# Sheet_Sensor.net
KiCad netlist of a schematic drawn in Altium Designer
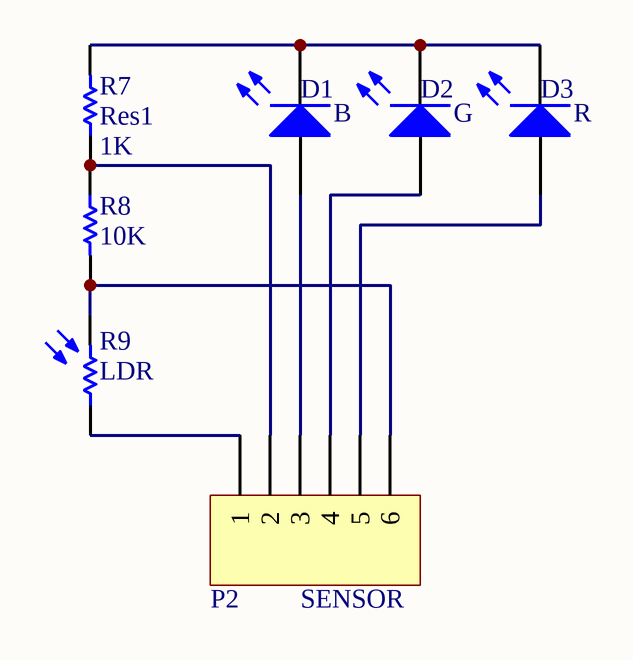
[diagram p0: Sheet_Sensor.SchDoc]

(export (version "E")
  (design (tool "Eeschema 10.0.6"))
  (components
    (comp (ref "D1")
      (value "B")
      (footprint "LED")
      (description "Typical RED GaAs LED")
      (fields (field (name "PUBLISHER") "Altium Limited"))
      (libsource (lib "Miscellaneous Devices") (part "LED1"))
    )
    (comp (ref "D2")
      (value "G")
      (footprint "LED")
      (description "Typical RED GaAs LED")
      (fields (field (name "PUBLISHER") "Altium Limited"))
      (libsource (lib "Miscellaneous Devices") (part "LED1"))
    )
    (comp (ref "D3")
      (value "R")
      (footprint "LED")
      (description "Typical RED GaAs LED")
      (fields (field (name "PUBLISHER") "Altium Limited"))
      (libsource (lib "Miscellaneous Devices") (part "LED1"))
    )
    (comp (ref "P2")
      (value "SENSOR")
      (footprint "H6")
      (description "Header, 6-Pin")
      (fields (field (name "PUBLISHER") "Altium Limited"))
      (libsource (lib "Miscellaneous Connectors") (part "Header 6"))
    )
    (comp (ref "R7")
      (value "Res1")
      (footprint "RES")
      (description "Resistor")
      (fields (field (name "ALTIUM_VALUE") "1K") (field (name "PUBLISHER") "Altium Limited"))
      (libsource (lib "Common Parts") (part "Res1"))
    )
    (comp (ref "R8")
      (value "10K")
      (footprint "RES")
      (description "Resistor")
      (fields (field (name "PUBLISHER") "Altium Limited"))
      (libsource (lib "Common Parts") (part "Res1"))
    )
    (comp (ref "R9")
      (value "LDR")
      (footprint "LDR")
      (description "Photoconductive Resistor, 200 kOhm, 100 V, 80 mW, -40 to 75 degC, 2-Pin THD, RoHS")
      (fields (field (name "MANUFACTURER") "Excelitas Technology"))
      (libsource (lib "Common Parts") (part "LDR"))
    )
  )
  (nets
    (net (code "1") (name "Net-(D1-A)") (class "Default")
      (node (ref "D1") (pin "1") (pinfunction "A_1") (pintype "passive"))
      (node (ref "P2") (pin "3") (pinfunction "3_3") (pintype "passive"))
    )
    (net (code "2") (name "Net-(D1-K)") (class "Default")
      (node (ref "D1") (pin "2") (pinfunction "K_2") (pintype "passive"))
      (node (ref "D2") (pin "2") (pinfunction "K_2") (pintype "passive"))
      (node (ref "D3") (pin "2") (pinfunction "K_2") (pintype "passive"))
      (node (ref "R7") (pin "2") (pinfunction "2_2") (pintype "passive"))
    )
    (net (code "3") (name "Net-(D2-A)") (class "Default")
      (node (ref "D2") (pin "1") (pinfunction "A_1") (pintype "passive"))
      (node (ref "P2") (pin "4") (pinfunction "4_4") (pintype "passive"))
    )
    (net (code "4") (name "Net-(D3-A)") (class "Default")
      (node (ref "D3") (pin "1") (pinfunction "A_1") (pintype "passive"))
      (node (ref "P2") (pin "5") (pinfunction "5_5") (pintype "passive"))
    )
    (net (code "5") (name "Net-(P2-Pad1)") (class "Default")
      (node (ref "P2") (pin "1") (pinfunction "1_1") (pintype "passive"))
      (node (ref "R9") (pin "1") (pinfunction "1_1") (pintype "passive"))
    )
    (net (code "6") (name "Net-(P2-Pad2)") (class "Default")
      (node (ref "P2") (pin "2") (pinfunction "2_2") (pintype "passive"))
      (node (ref "R7") (pin "1") (pinfunction "1_1") (pintype "passive"))
      (node (ref "R8") (pin "1") (pinfunction "1_1") (pintype "passive"))
    )
    (net (code "7") (name "Net-(P2-Pad6)") (class "Default")
      (node (ref "P2") (pin "6") (pinfunction "6_6") (pintype "passive"))
      (node (ref "R8") (pin "2") (pinfunction "2_2") (pintype "passive"))
      (node (ref "R9") (pin "2") (pinfunction "2_2") (pintype "passive"))
    )
  )
)
